# Solar_USB.net
KiCad netlist of a schematic drawn in EAGLE
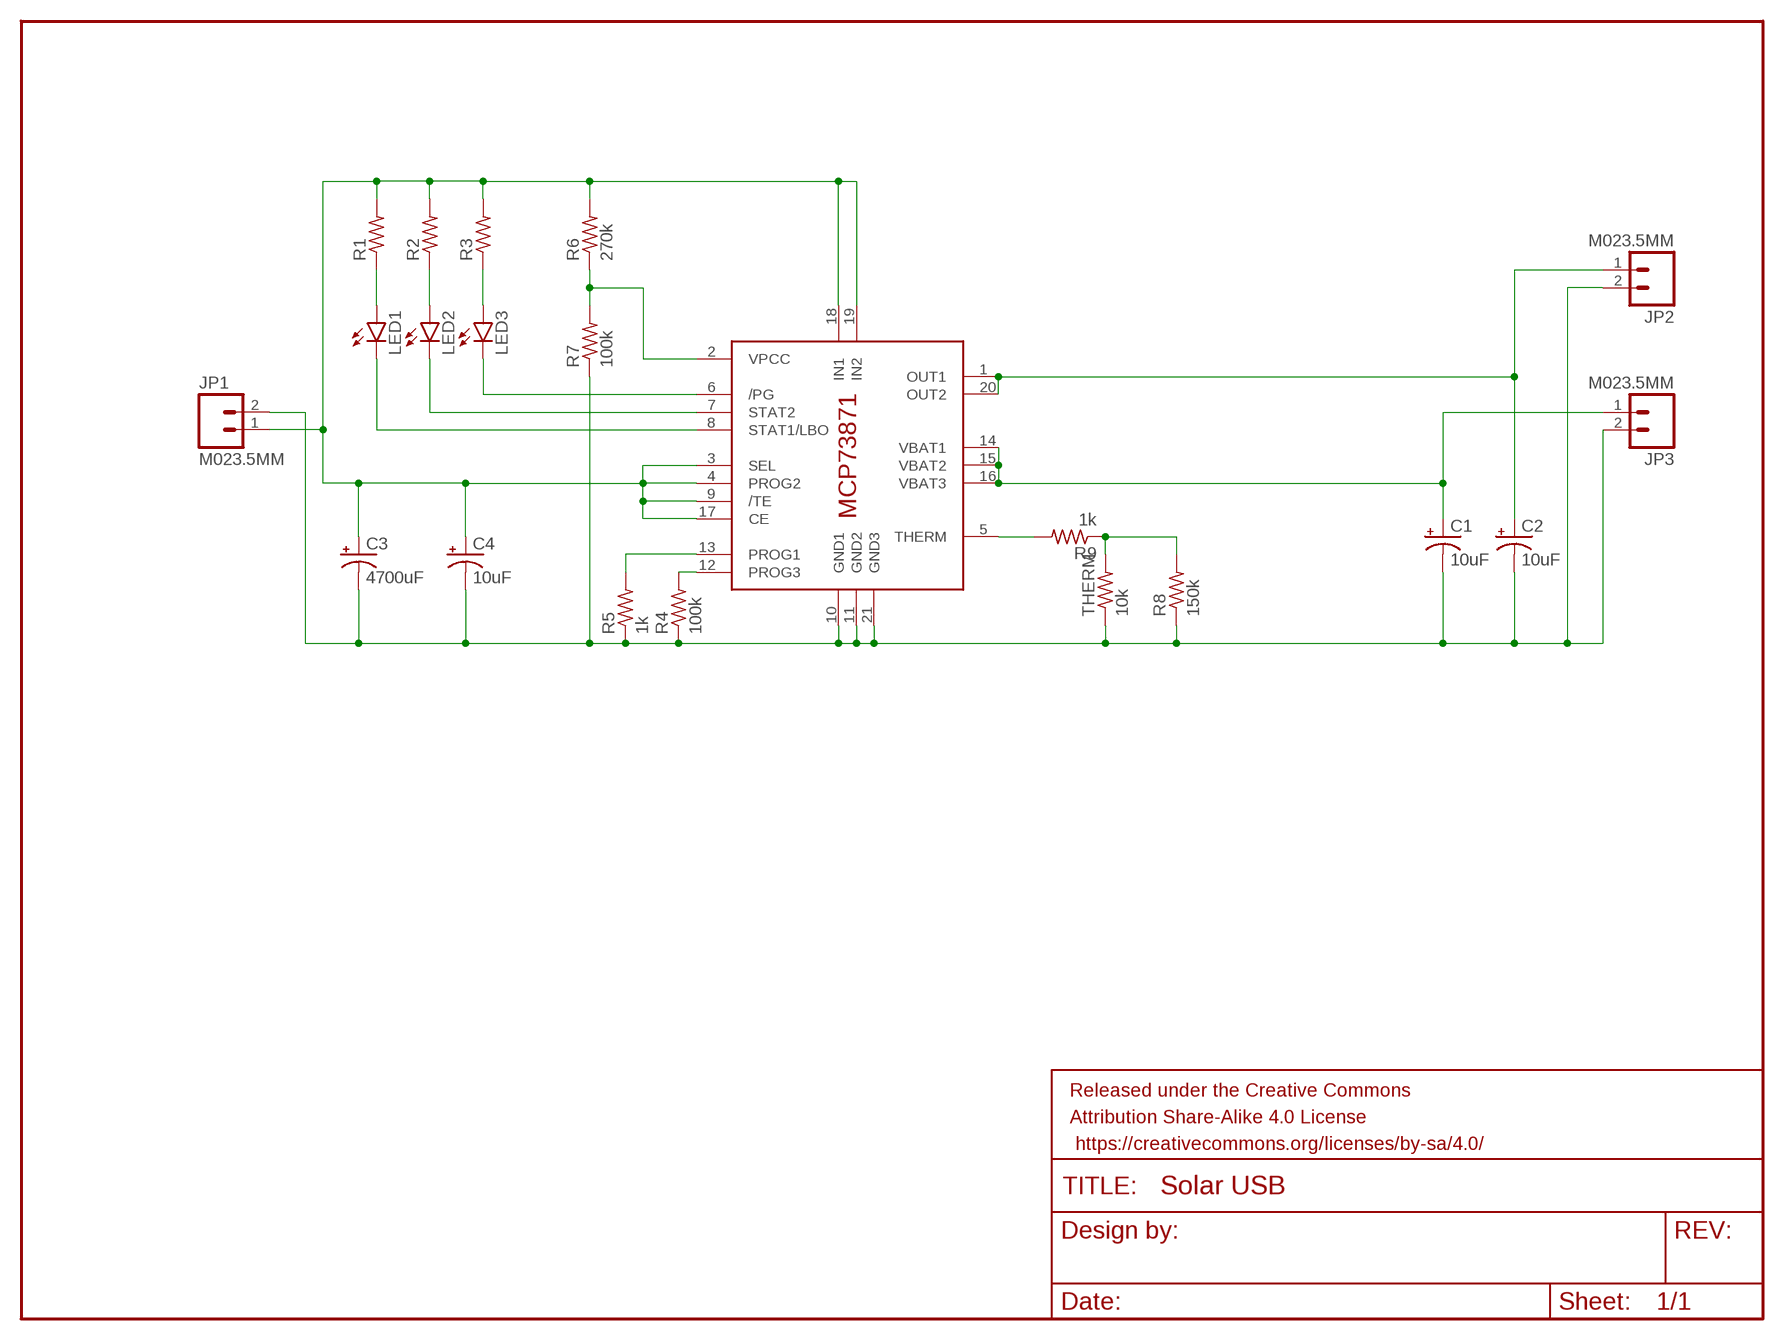
[diagram p0: schematic, sheet 1]

(export (version "E")
  (design (tool "Eeschema 10.0.6"))
  (components
    (comp (ref "C1")
      (value "10uF")
      (footprint "eagle-import:E2,5-5")
      (libsource (lib "eagle-import") (part "CPOL-USE2.5-5"))
    )
    (comp (ref "C2")
      (value "10uF")
      (footprint "eagle-import:E2,5-5")
      (libsource (lib "eagle-import") (part "CPOL-USE2.5-5"))
    )
    (comp (ref "C3")
      (value "4700uF")
      (footprint "eagle-import:E7,5-16")
      (libsource (lib "eagle-import") (part "CPOL-USE7.5-16"))
    )
    (comp (ref "C4")
      (value "10uF")
      (footprint "eagle-import:E2,5-5")
      (libsource (lib "eagle-import") (part "CPOL-USE2.5-5"))
    )
    (comp (ref "FRAME1")
      (value "FRAME-LETTER")
      (footprint "eagle-import:CREATIVE_COMMONS")
      (libsource (lib "eagle-import") (part "FRAME-LETTER"))
    )
    (comp (ref "IC1")
      (value "MCP73871")
      (footprint "eagle-import:QFN20")
      (libsource (lib "eagle-import") (part "MCP73871"))
    )
    (comp (ref "JP1")
      (value "M023.5MM")
      (footprint "eagle-import:SCREWTERMINAL-3.5MM-2")
      (libsource (lib "eagle-import") (part "M023.5MM"))
    )
    (comp (ref "JP2")
      (value "M023.5MM")
      (footprint "eagle-import:SCREWTERMINAL-3.5MM-2")
      (libsource (lib "eagle-import") (part "M023.5MM"))
    )
    (comp (ref "JP3")
      (value "M023.5MM")
      (footprint "eagle-import:SCREWTERMINAL-3.5MM-2")
      (libsource (lib "eagle-import") (part "M023.5MM"))
    )
    (comp (ref "LED1")
      (value "LED5MM")
      (footprint "eagle-import:LED5MM")
      (libsource (lib "eagle-import") (part "LED5MM"))
    )
    (comp (ref "LED2")
      (value "LED5MM")
      (footprint "eagle-import:LED5MM")
      (libsource (lib "eagle-import") (part "LED5MM"))
    )
    (comp (ref "LED3")
      (value "LED5MM")
      (footprint "eagle-import:LED5MM")
      (libsource (lib "eagle-import") (part "LED5MM"))
    )
    (comp (ref "R1")
      (value "R-US_0207/10")
      (footprint "eagle-import:0207_10")
      (libsource (lib "eagle-import") (part "R-US_0207/10"))
    )
    (comp (ref "R2")
      (value "R-US_0207/10")
      (footprint "eagle-import:0207_10")
      (libsource (lib "eagle-import") (part "R-US_0207/10"))
    )
    (comp (ref "R3")
      (value "R-US_0207/10")
      (footprint "eagle-import:0207_10")
      (libsource (lib "eagle-import") (part "R-US_0207/10"))
    )
    (comp (ref "R4")
      (value "100k")
      (footprint "eagle-import:0207_10")
      (libsource (lib "eagle-import") (part "R-US_0207/10"))
    )
    (comp (ref "R5")
      (value "1k")
      (footprint "eagle-import:0207_10")
      (libsource (lib "eagle-import") (part "R-US_0207/10"))
    )
    (comp (ref "R6")
      (value "270k")
      (footprint "eagle-import:0207_10")
      (libsource (lib "eagle-import") (part "R-US_0207/10"))
    )
    (comp (ref "R7")
      (value "100k")
      (footprint "eagle-import:0207_10")
      (libsource (lib "eagle-import") (part "R-US_0207/10"))
    )
    (comp (ref "R8")
      (value "150k")
      (footprint "eagle-import:0207_10")
      (libsource (lib "eagle-import") (part "R-US_0207/10"))
    )
    (comp (ref "R9")
      (value "1k")
      (footprint "eagle-import:0207_10")
      (libsource (lib "eagle-import") (part "R-US_0207/10"))
    )
    (comp (ref "THERM")
      (value "10k")
      (footprint "eagle-import:0207_10")
      (libsource (lib "eagle-import") (part "R-US_0207/10"))
    )
  )
  (nets
    (net (code "1") (name "Net-(IC1-CE)") (class "Default")
      (node (ref "C3") (pin "+") (pinfunction "+_+") (pintype "passive"))
      (node (ref "C4") (pin "+") (pinfunction "+_+") (pintype "passive"))
      (node (ref "IC1") (pin "17") (pinfunction "CE_17") (pintype "input"))
      (node (ref "IC1") (pin "18") (pinfunction "IN1_18") (pintype "input"))
      (node (ref "IC1") (pin "19") (pinfunction "IN2_19") (pintype "input"))
      (node (ref "IC1") (pin "3") (pinfunction "SEL_3") (pintype "input"))
      (node (ref "IC1") (pin "4") (pinfunction "PROG2_4") (pintype "input"))
      (node (ref "IC1") (pin "9") (pinfunction "/TE_9") (pintype "input"))
      (node (ref "JP1") (pin "1") (pinfunction "1_1") (pintype "passive"))
      (node (ref "R1") (pin "2") (pinfunction "2_2") (pintype "passive"))
      (node (ref "R2") (pin "2") (pinfunction "2_2") (pintype "passive"))
      (node (ref "R3") (pin "2") (pinfunction "2_2") (pintype "passive"))
      (node (ref "R6") (pin "2") (pinfunction "2_2") (pintype "passive"))
    )
    (net (code "2") (name "Net-(IC1-GND1)") (class "Default")
      (node (ref "C1") (pin "-") (pinfunction "-_-") (pintype "passive"))
      (node (ref "C2") (pin "-") (pinfunction "-_-") (pintype "passive"))
      (node (ref "C3") (pin "-") (pinfunction "-_-") (pintype "passive"))
      (node (ref "C4") (pin "-") (pinfunction "-_-") (pintype "passive"))
      (node (ref "IC1") (pin "10") (pinfunction "GND1_10") (pintype "power_in"))
      (node (ref "IC1") (pin "11") (pinfunction "GND2_11") (pintype "power_in"))
      (node (ref "IC1") (pin "21") (pinfunction "GND3_21") (pintype "bidirectional"))
      (node (ref "JP1") (pin "2") (pinfunction "2_2") (pintype "passive"))
      (node (ref "JP2") (pin "2") (pinfunction "2_2") (pintype "passive"))
      (node (ref "JP3") (pin "2") (pinfunction "2_2") (pintype "passive"))
      (node (ref "R4") (pin "1") (pinfunction "1_1") (pintype "passive"))
      (node (ref "R5") (pin "1") (pinfunction "1_1") (pintype "passive"))
      (node (ref "R7") (pin "1") (pinfunction "1_1") (pintype "passive"))
      (node (ref "R8") (pin "1") (pinfunction "1_1") (pintype "passive"))
      (node (ref "THERM") (pin "1") (pinfunction "1_1") (pintype "passive"))
    )
    (net (code "3") (name "Net-(IC1-OUT1)") (class "Default")
      (node (ref "C2") (pin "+") (pinfunction "+_+") (pintype "passive"))
      (node (ref "IC1") (pin "1") (pinfunction "OUT1_1") (pintype "output"))
      (node (ref "IC1") (pin "20") (pinfunction "OUT2_20") (pintype "output"))
      (node (ref "JP2") (pin "1") (pinfunction "1_1") (pintype "passive"))
    )
    (net (code "4") (name "Net-(IC1-PROG1)") (class "Default")
      (node (ref "IC1") (pin "13") (pinfunction "PROG1_13") (pintype "input"))
      (node (ref "R5") (pin "2") (pinfunction "2_2") (pintype "passive"))
    )
    (net (code "5") (name "Net-(IC1-PROG3)") (class "Default")
      (node (ref "IC1") (pin "12") (pinfunction "PROG3_12") (pintype "input"))
      (node (ref "R4") (pin "2") (pinfunction "2_2") (pintype "passive"))
    )
    (net (code "6") (name "Net-(IC1-STAT1{slash}LBO)") (class "Default")
      (node (ref "IC1") (pin "8") (pinfunction "STAT1/LBO_8") (pintype "output"))
      (node (ref "LED1") (pin "K") (pinfunction "C_K") (pintype "passive"))
    )
    (net (code "7") (name "Net-(IC1-STAT2)") (class "Default")
      (node (ref "IC1") (pin "7") (pinfunction "STAT2_7") (pintype "output"))
      (node (ref "LED2") (pin "K") (pinfunction "C_K") (pintype "passive"))
    )
    (net (code "8") (name "Net-(IC1-THERM)") (class "Default")
      (node (ref "IC1") (pin "5") (pinfunction "THERM_5") (pintype "input"))
      (node (ref "R9") (pin "2") (pinfunction "2_2") (pintype "passive"))
    )
    (net (code "9") (name "Net-(IC1-VBAT1)") (class "Default")
      (node (ref "C1") (pin "+") (pinfunction "+_+") (pintype "passive"))
      (node (ref "IC1") (pin "14") (pinfunction "VBAT1_14") (pintype "output"))
      (node (ref "IC1") (pin "15") (pinfunction "VBAT2_15") (pintype "output"))
      (node (ref "IC1") (pin "16") (pinfunction "VBAT3_16") (pintype "output"))
      (node (ref "JP3") (pin "1") (pinfunction "1_1") (pintype "passive"))
    )
    (net (code "10") (name "Net-(IC1-VPCC)") (class "Default")
      (node (ref "IC1") (pin "2") (pinfunction "VPCC_2") (pintype "input"))
      (node (ref "R6") (pin "1") (pinfunction "1_1") (pintype "passive"))
      (node (ref "R7") (pin "2") (pinfunction "2_2") (pintype "passive"))
    )
    (net (code "11") (name "Net-(IC1-{slash}PG)") (class "Default")
      (node (ref "IC1") (pin "6") (pinfunction "/PG_6") (pintype "output"))
      (node (ref "LED3") (pin "K") (pinfunction "C_K") (pintype "passive"))
    )
    (net (code "12") (name "Net-(LED1-PadA)") (class "Default")
      (node (ref "LED1") (pin "A") (pinfunction "A_A") (pintype "passive"))
      (node (ref "R1") (pin "1") (pinfunction "1_1") (pintype "passive"))
    )
    (net (code "13") (name "Net-(LED2-PadA)") (class "Default")
      (node (ref "LED2") (pin "A") (pinfunction "A_A") (pintype "passive"))
      (node (ref "R2") (pin "1") (pinfunction "1_1") (pintype "passive"))
    )
    (net (code "14") (name "Net-(LED3-PadA)") (class "Default")
      (node (ref "LED3") (pin "A") (pinfunction "A_A") (pintype "passive"))
      (node (ref "R3") (pin "1") (pinfunction "1_1") (pintype "passive"))
    )
    (net (code "15") (name "Net-(R8-Pad2)") (class "Default")
      (node (ref "R8") (pin "2") (pinfunction "2_2") (pintype "passive"))
      (node (ref "R9") (pin "1") (pinfunction "1_1") (pintype "passive"))
      (node (ref "THERM") (pin "2") (pinfunction "2_2") (pintype "passive"))
    )
  )
)
